# DC.net
KiCad netlist of a schematic drawn in Altium Designer
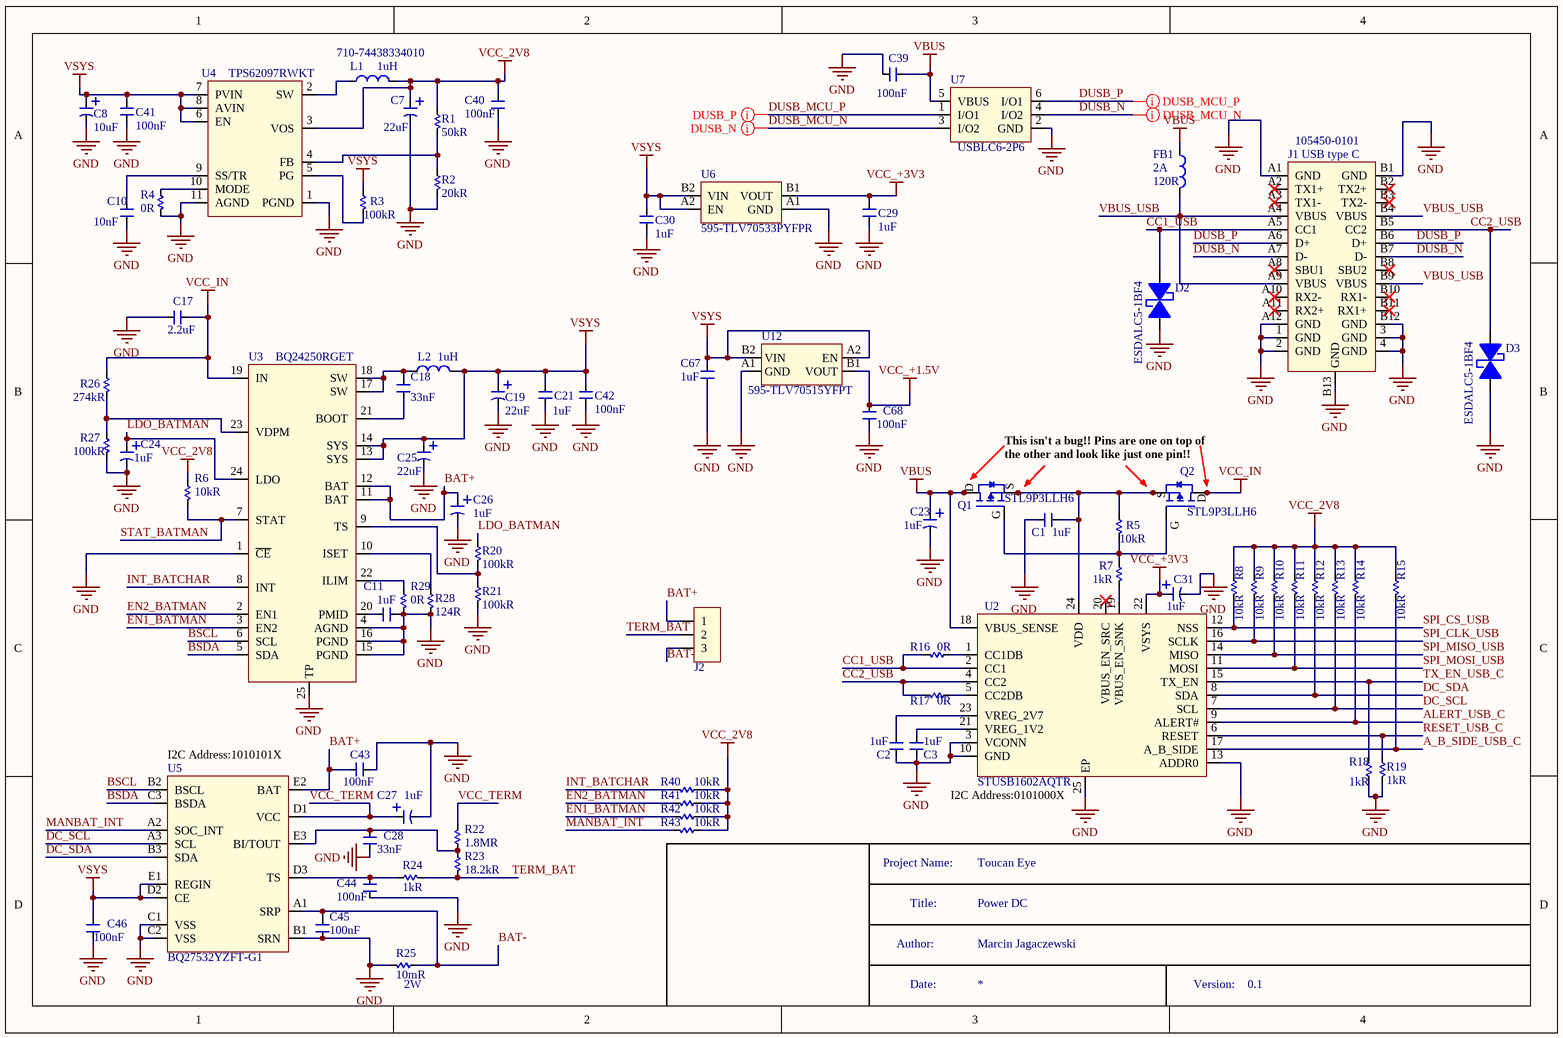
[diagram p0: DC.SchDoc]

(export (version "E")
  (design (tool "Eeschema 10.0.6"))
  (components
    (comp (ref "C1")
      (value "C0402_1uF_TMK105BJ105MV-F")
      (footprint "C_0402")
      (description "CAP CER 1UF 25V X5R 0402")
      (fields
        (field (name "MANUFACTURER") "Taiyo Yuden")
        (field (name "MANUFACTURER PART NUMBER") "TMK105BJ105MV-F")
        (field (name "CAPACITANCE") "1uF")
      )
      (libsource (lib "CAP") (part "C0402_1uF_TMK105BJ105MV-F"))
    )
    (comp (ref "C2")
      (value "C0402_1uF_TMK105BJ105MV-F")
      (footprint "C_0402")
      (description "CAP CER 1UF 25V X5R 0402")
      (fields
        (field (name "MANUFACTURER") "Taiyo Yuden")
        (field (name "MANUFACTURER PART NUMBER") "TMK105BJ105MV-F")
        (field (name "CAPACITANCE") "1uF")
      )
      (libsource (lib "CAP") (part "C0402_1uF_TMK105BJ105MV-F"))
    )
    (comp (ref "C3")
      (value "C0402_1uF_TMK105BJ105MV-F")
      (footprint "C_0402")
      (description "CAP CER 1UF 25V X5R 0402")
      (fields
        (field (name "MANUFACTURER") "Taiyo Yuden")
        (field (name "MANUFACTURER PART NUMBER") "TMK105BJ105MV-F")
        (field (name "CAPACITANCE") "1uF")
      )
      (libsource (lib "CAP") (part "C0402_1uF_TMK105BJ105MV-F"))
    )
    (comp (ref "C7")
      (value "C_22u_TANTAL_A_T491A226K006AT")
      (footprint "C_3216")
      (description "Cap Tant Solid 22uF 6.3V A CASE 10% (3.2 X 1.6 X 1.6mm) SMD 3216-18 4 Ohm 125C T/R")
      (fields
        (field (name "MANUFACTURER") "KEMET")
        (field (name "MANUFACTURER PART NUMBER") "T491A226K006AT")
        (field (name "CAPACITANCE") "22uF")
      )
      (libsource (lib "CAP") (part "C_22u_TANTAL_A_T491A226K006AT"))
    )
    (comp (ref "C8")
      (value "C_10u_TANTAL_A_T491A106K010AT7280")
      (footprint "C_3216")
      (description "CAP TANT 10UF 10V 10% 1206")
      (fields
        (field (name "MANUFACTURER") "KEMET")
        (field (name "MANUFACTURER PART NUMBER") "T491A106K010AT7280")
        (field (name "CAPACITANCE") "10uF")
      )
      (libsource (lib "CAP") (part "C_10u_TANTAL_A_T491A106K010AT7280"))
    )
    (comp (ref "C10")
      (value "C0402_10n_C0402C103K4PACTU")
      (footprint "C_0402")
      (description ".010UF 16.0V")
      (fields
        (field (name "MANUFACTURER") "KEMET")
        (field (name "MANUFACTURER PART NUMBER") "C0402C103K4PACTU")
        (field (name "CAPACITANCE") "10nF")
      )
      (libsource (lib "CAP") (part "C0402_10n_C0402C103K4PACTU"))
    )
    (comp (ref "C11")
      (value "C0402_1uF_TMK105BJ105MV-F")
      (footprint "C_0402")
      (description "CAP CER 1UF 25V X5R 0402")
      (fields
        (field (name "MANUFACTURER") "Taiyo Yuden")
        (field (name "MANUFACTURER PART NUMBER") "TMK105BJ105MV-F")
        (field (name "CAPACITANCE") "1uF")
      )
      (libsource (lib "CAP") (part "C0402_1uF_TMK105BJ105MV-F"))
    )
    (comp (ref "C17")
      (value "C0402_2.2u_GRT155R61E225KE13D")
      (footprint "C_0402")
      (description "2.2µF 25V Ceramic Capacitor X5R 0402 (1005 Metric) 0.039\" L x 0.020\" W (1.00mm x 0.50mm)")
      (fields
        (field (name "MANUFACTURER") "Murata")
        (field (name "MANUFACTURER PART NUMBER") "GRT155R61E225KE13D")
        (field (name "CAPACITANCE") "2.2uF")
      )
      (libsource (lib "CAP") (part "C0402_2.2u_GRT155R61E225KE13D"))
    )
    (comp (ref "C18")
      (value "C0402_33n_GCM155R71E333KA55D")
      (footprint "C_0402")
      (description "Multilayer Ceramic Capacitors MLCC - SMD/SMT .033uF 25Volts 10%")
      (fields
        (field (name "MANUFACTURER") "Murata")
        (field (name "MANUFACTURER PART NUMBER") "GCM155R71E333KA55D")
        (field (name "CAPACITANCE") "33nF")
      )
      (libsource (lib "CAP") (part "C0402_33n_GCM155R71E333KA55D"))
    )
    (comp (ref "C19")
      (value "C_22u_TANTAL_A_T491A226K006AT")
      (footprint "C_3216")
      (description "Cap Tant Solid 22uF 6.3V A CASE 10% (3.2 X 1.6 X 1.6mm) SMD 3216-18 4 Ohm 125C T/R")
      (fields
        (field (name "MANUFACTURER") "KEMET")
        (field (name "MANUFACTURER PART NUMBER") "T491A226K006AT")
        (field (name "CAPACITANCE") "22uF")
      )
      (libsource (lib "CAP") (part "C_22u_TANTAL_A_T491A226K006AT"))
    )
    (comp (ref "C21")
      (value "C0402_1uF_TMK105BJ105MV-F")
      (footprint "C_0402")
      (description "CAP CER 1UF 25V X5R 0402")
      (fields
        (field (name "MANUFACTURER") "Taiyo Yuden")
        (field (name "MANUFACTURER PART NUMBER") "TMK105BJ105MV-F")
        (field (name "CAPACITANCE") "1uF")
      )
      (libsource (lib "CAP") (part "C0402_1uF_TMK105BJ105MV-F"))
    )
    (comp (ref "C23")
      (value "C_1u_TANTAL_A_293D105X0025A2TE3")
      (footprint "C_3216")
      (description "CAP TANT 1UF 25V 20% 1206")
      (fields
        (field (name "MANUFACTURER") "Vishay Sprague")
        (field (name "MANUFACTURER PART NUMBER") "293D105X0025A2TE3")
        (field (name "CAPACITANCE") "1uF")
      )
      (libsource (lib "CAP") (part "C_1u_TANTAL_A_293D105X0025A2TE3"))
    )
    (comp (ref "C24")
      (value "C_1u_TANTAL_A_293D105X0025A2TE3")
      (footprint "C_3216")
      (description "CAP TANT 1UF 25V 20% 1206")
      (fields
        (field (name "MANUFACTURER") "Vishay Sprague")
        (field (name "MANUFACTURER PART NUMBER") "293D105X0025A2TE3")
        (field (name "CAPACITANCE") "1uF")
      )
      (libsource (lib "CAP") (part "C_1u_TANTAL_A_293D105X0025A2TE3"))
    )
    (comp (ref "C25")
      (value "C_22u_TANTAL_A_T491A226K006AT")
      (footprint "C_3216")
      (description "Cap Tant Solid 22uF 6.3V A CASE 10% (3.2 X 1.6 X 1.6mm) SMD 3216-18 4 Ohm 125C T/R")
      (fields
        (field (name "MANUFACTURER") "KEMET")
        (field (name "MANUFACTURER PART NUMBER") "T491A226K006AT")
        (field (name "CAPACITANCE") "22uF")
      )
      (libsource (lib "CAP") (part "C_22u_TANTAL_A_T491A226K006AT"))
    )
    (comp (ref "C26")
      (value "C_1u_TANTAL_A_293D105X0025A2TE3")
      (footprint "C_3216")
      (description "CAP TANT 1UF 25V 20% 1206")
      (fields
        (field (name "MANUFACTURER") "Vishay Sprague")
        (field (name "MANUFACTURER PART NUMBER") "293D105X0025A2TE3")
        (field (name "CAPACITANCE") "1uF")
      )
      (libsource (lib "CAP") (part "C_1u_TANTAL_A_293D105X0025A2TE3"))
    )
    (comp (ref "C27")
      (value "C_1u_TANTAL_A_293D105X0025A2TE3")
      (footprint "C_3216")
      (description "CAP TANT 1UF 25V 20% 1206")
      (fields
        (field (name "MANUFACTURER") "Vishay Sprague")
        (field (name "MANUFACTURER PART NUMBER") "293D105X0025A2TE3")
        (field (name "CAPACITANCE") "1uF")
      )
      (libsource (lib "CAP") (part "C_1u_TANTAL_A_293D105X0025A2TE3"))
    )
    (comp (ref "C28")
      (value "C0402_33n_GCM155R71E333KA55D")
      (footprint "C_0402")
      (description "Multilayer Ceramic Capacitors MLCC - SMD/SMT .033uF 25Volts 10%")
      (fields
        (field (name "MANUFACTURER") "Murata")
        (field (name "MANUFACTURER PART NUMBER") "GCM155R71E333KA55D")
        (field (name "CAPACITANCE") "33nF")
      )
      (libsource (lib "CAP") (part "C0402_33n_GCM155R71E333KA55D"))
    )
    (comp (ref "C29")
      (value "C0402_1uF_TMK105BJ105MV-F")
      (footprint "C_0402")
      (description "CAP CER 1UF 25V X5R 0402")
      (fields
        (field (name "MANUFACTURER") "Taiyo Yuden")
        (field (name "MANUFACTURER PART NUMBER") "TMK105BJ105MV-F")
        (field (name "CAPACITANCE") "1uF")
      )
      (libsource (lib "CAP") (part "C0402_1uF_TMK105BJ105MV-F"))
    )
    (comp (ref "C30")
      (value "C0402_1uF_TMK105BJ105MV-F")
      (footprint "C_0402")
      (description "CAP CER 1UF 25V X5R 0402")
      (fields
        (field (name "MANUFACTURER") "Taiyo Yuden")
        (field (name "MANUFACTURER PART NUMBER") "TMK105BJ105MV-F")
        (field (name "CAPACITANCE") "1uF")
      )
      (libsource (lib "CAP") (part "C0402_1uF_TMK105BJ105MV-F"))
    )
    (comp (ref "C31")
      (value "C_1u_TANTAL_A_293D105X0025A2TE3")
      (footprint "C_3216")
      (description "CAP TANT 1UF 25V 20% 1206")
      (fields
        (field (name "MANUFACTURER") "Vishay Sprague")
        (field (name "MANUFACTURER PART NUMBER") "293D105X0025A2TE3")
        (field (name "CAPACITANCE") "1uF")
      )
      (libsource (lib "CAP") (part "C_1u_TANTAL_A_293D105X0025A2TE3"))
    )
    (comp (ref "C39")
      (value "C0201_100n_GRM033R6YA104KE14D")
      (footprint "C_0201")
      (description "Multilayer Ceramic Capacitors MLCC - SMD/SMT 0201 0.10uF 35volts *Derate Voltage/Temp")
      (fields
        (field (name "MANUFACTURER") "Murata")
        (field (name "MANUFACTURER PART NUMBER") "GRM033R6YA104KE14D")
        (field (name "CAPACITANCE") "100nF")
      )
      (libsource (lib "CAP") (part "C0201_100n_GRM033R6YA104KE14D"))
    )
    (comp (ref "C40")
      (value "C0201_100n_GRM033R6YA104KE14D")
      (footprint "C_0201")
      (description "Multilayer Ceramic Capacitors MLCC - SMD/SMT 0201 0.10uF 35volts *Derate Voltage/Temp")
      (fields
        (field (name "MANUFACTURER") "Murata")
        (field (name "MANUFACTURER PART NUMBER") "GRM033R6YA104KE14D")
        (field (name "CAPACITANCE") "100nF")
      )
      (libsource (lib "CAP") (part "C0201_100n_GRM033R6YA104KE14D"))
    )
    (comp (ref "C41")
      (value "C0201_100n_GRM033R6YA104KE14D")
      (footprint "C_0201")
      (description "Multilayer Ceramic Capacitors MLCC - SMD/SMT 0201 0.10uF 35volts *Derate Voltage/Temp")
      (fields
        (field (name "MANUFACTURER") "Murata")
        (field (name "MANUFACTURER PART NUMBER") "GRM033R6YA104KE14D")
        (field (name "CAPACITANCE") "100nF")
      )
      (libsource (lib "CAP") (part "C0201_100n_GRM033R6YA104KE14D"))
    )
    (comp (ref "C42")
      (value "C0201_100n_GRM033R6YA104KE14D")
      (footprint "C_0201")
      (description "Multilayer Ceramic Capacitors MLCC - SMD/SMT 0201 0.10uF 35volts *Derate Voltage/Temp")
      (fields
        (field (name "MANUFACTURER") "Murata")
        (field (name "MANUFACTURER PART NUMBER") "GRM033R6YA104KE14D")
        (field (name "CAPACITANCE") "100nF")
      )
      (libsource (lib "CAP") (part "C0201_100n_GRM033R6YA104KE14D"))
    )
    (comp (ref "C43")
      (value "C0201_100n_GRM033R6YA104KE14D")
      (footprint "C_0201")
      (description "Multilayer Ceramic Capacitors MLCC - SMD/SMT 0201 0.10uF 35volts *Derate Voltage/Temp")
      (fields
        (field (name "MANUFACTURER") "Murata")
        (field (name "MANUFACTURER PART NUMBER") "GRM033R6YA104KE14D")
        (field (name "CAPACITANCE") "100nF")
      )
      (libsource (lib "CAP") (part "C0201_100n_GRM033R6YA104KE14D"))
    )
    (comp (ref "C44")
      (value "C0201_100n_GRM033R6YA104KE14D")
      (footprint "C_0201")
      (description "Multilayer Ceramic Capacitors MLCC - SMD/SMT 0201 0.10uF 35volts *Derate Voltage/Temp")
      (fields
        (field (name "MANUFACTURER") "Murata")
        (field (name "MANUFACTURER PART NUMBER") "GRM033R6YA104KE14D")
        (field (name "CAPACITANCE") "100nF")
      )
      (libsource (lib "CAP") (part "C0201_100n_GRM033R6YA104KE14D"))
    )
    (comp (ref "C45")
      (value "C0201_100n_GRM033R6YA104KE14D")
      (footprint "C_0201")
      (description "Multilayer Ceramic Capacitors MLCC - SMD/SMT 0201 0.10uF 35volts *Derate Voltage/Temp")
      (fields
        (field (name "MANUFACTURER") "Murata")
        (field (name "MANUFACTURER PART NUMBER") "GRM033R6YA104KE14D")
        (field (name "CAPACITANCE") "100nF")
      )
      (libsource (lib "CAP") (part "C0201_100n_GRM033R6YA104KE14D"))
    )
    (comp (ref "C46")
      (value "C0201_100n_GRM033R6YA104KE14D")
      (footprint "C_0201")
      (description "Multilayer Ceramic Capacitors MLCC - SMD/SMT 0201 0.10uF 35volts *Derate Voltage/Temp")
      (fields
        (field (name "MANUFACTURER") "Murata")
        (field (name "MANUFACTURER PART NUMBER") "GRM033R6YA104KE14D")
        (field (name "CAPACITANCE") "100nF")
      )
      (libsource (lib "CAP") (part "C0201_100n_GRM033R6YA104KE14D"))
    )
    (comp (ref "C67")
      (value "C0402_1uF_TMK105BJ105MV-F")
      (footprint "C_0402")
      (description "CAP CER 1UF 25V X5R 0402")
      (fields
        (field (name "MANUFACTURER") "Taiyo Yuden")
        (field (name "MANUFACTURER PART NUMBER") "TMK105BJ105MV-F")
        (field (name "CAPACITANCE") "1uF")
      )
      (libsource (lib "CAP") (part "C0402_1uF_TMK105BJ105MV-F"))
    )
    (comp (ref "C68")
      (value "C0201_100n_GRM033R6YA104KE14D")
      (footprint "C_0201")
      (description "Multilayer Ceramic Capacitors MLCC - SMD/SMT 0201 0.10uF 35volts *Derate Voltage/Temp")
      (fields
        (field (name "MANUFACTURER") "Murata")
        (field (name "MANUFACTURER PART NUMBER") "GRM033R6YA104KE14D")
        (field (name "CAPACITANCE") "100nF")
      )
      (libsource (lib "CAP") (part "C0201_100n_GRM033R6YA104KE14D"))
    )
    (comp (ref "D2")
      (value "ESDALC5-1BF4")
      (footprint "DFN35P60X32-2N")
      (description "ESD Suppressor TVS 30KV 2-Pin Case 0201 T/R")
      (fields (field (name "MANUFACTURER") "STMicroelectronics"))
      (libsource (lib "DIO") (part "ESDALC5-1BF4"))
    )
    (comp (ref "D3")
      (value "ESDALC5-1BF4")
      (footprint "DFN35P60X32-2N")
      (description "ESD Suppressor TVS 30KV 2-Pin Case 0201 T/R")
      (fields (field (name "MANUFACTURER") "STMicroelectronics"))
      (libsource (lib "DIO") (part "ESDALC5-1BF4"))
    )
    (comp (ref "FB1")
      (value "BLM18PG-121SN1D")
      (footprint "L_0603")
      (description "Ferrite Beads Multi-Layer 120Ohm 25% 100MHz 2A 50mOhm DCR 0603 Paper T/R")
      (fields
        (field (name "MANUFACTURER") "Murata")
        (field (name "TOLERANCE") "25%")
        (field (name "DC CURRENT") "2A")
        (field (name "IMPEDANCE") "120R")
      )
      (libsource (lib "IND") (part "BLM18PG-121SN1D"))
    )
    (comp (ref "J1")
      (value "105450-0101")
      (footprint "USB TYPE C (MOLEX)")
      (fields (field (name "MANUFACTURER") "Molex") (field (name "CONNECTOR TYPE") "USB type C"))
      (libsource (lib "CONN") (part "105450-0101"))
    )
    (comp (ref "J2")
      (value "Goldpin 3x1.27mm NDI")
      (footprint "HEADER 3x1.27mm")
      (libsource (lib "Holes") (part "Goldpin 3x1.27mm NDI"))
    )
    (comp (ref "L1")
      (value "L_1u_3x3_74438334010")
      (footprint "L_3x3")
      (fields
        (field (name "MANUFACTURER") "Wurth Electronics")
        (field (name "MANUFACTURER PART NUMBER") "74438334010")
        (field (name "TOLERANCE") "20%")
        (field (name "INDUCTANCE") "1uH")
        (field (name "SUPPLIER PART NUMBER 1") "710-74438334010")
      )
      (libsource (lib "IND") (part "L_1u_3x3_74438334010"))
    )
    (comp (ref "L2")
      (value "l_1U_3X3_74438336010")
      (footprint "L_3x3")
      (fields
        (field (name "MANUFACTURER") "Wurth Electronics")
        (field (name "MANUFACTURER PART NUMBER") "74438336010")
        (field (name "TOLERANCE") "20%")
        (field (name "INDUCTANCE") "1uH")
      )
      (libsource (lib "IND") (part "l_1U_3X3_74438336010"))
    )
    (comp (ref "Q1")
      (value "STL9P3LLH6")
      (footprint "PowerFLAT")
      (description "POWER MOSFET")
      (fields (field (name "MANUFACTURER") "STMicroelectronics"))
      (libsource (lib "DIO") (part "STL9P3LLH6"))
    )
    (comp (ref "Q2")
      (value "STL9P3LLH6")
      (footprint "PowerFLAT")
      (description "POWER MOSFET")
      (fields (field (name "MANUFACTURER") "STMicroelectronics"))
      (libsource (lib "DIO") (part "STL9P3LLH6"))
    )
    (comp (ref "R1")
      (value "R0402_50k_CRCW040250K0FKED")
      (footprint "R_0402")
      (description "Thick Film Resistors - SMD 1/16watt 50Kohms 1% Non Standard")
      (fields
        (field (name "MANUFACTURER") "Vishay Dale")
        (field (name "MANUFACTURER PART NUMBER") "CRCW040250K0FKED")
        (field (name "RESISTANCE") "50kR")
      )
      (libsource (lib "RES") (part "R0402_50k_CRCW040250K0FKED"))
    )
    (comp (ref "R2")
      (value "R0402_20k_ERJ-2RKF2002X")
      (footprint "R_0402")
      (description "Res Thick Film 0402 20K Ohm 1% 0.1W(1/10W) ±100ppm/C Molded SMD Automotive T/R")
      (fields
        (field (name "MANUFACTURER") "Panasonic ECG")
        (field (name "MANUFACTURER PART NUMBER") "ERJ-2RKF2002X")
        (field (name "RESISTANCE") "20kR")
      )
      (libsource (lib "RES") (part "R0402_20k_ERJ-2RKF2002X"))
    )
    (comp (ref "R3")
      (value "R0402_100k_ERJ-2RKF1003X")
      (footprint "R_0402")
      (description "Res Thick Film 0402 100K Ohm 1% 0.1W(1/10W) ±100ppm/C Molded SMD Automotive Punched T/R")
      (fields
        (field (name "MANUFACTURER") "Panasonic ECG")
        (field (name "MANUFACTURER PART NUMBER") "ERJ-2RKF1003X")
        (field (name "RESISTANCE") "100kR")
      )
      (libsource (lib "RES") (part "R0402_100k_ERJ-2RKF1003X"))
    )
    (comp (ref "R4")
      (value "R0402_0ohm_RC0402FR-070RL")
      (footprint "R_0402")
      (description "Thick Film Resistors - SMD 0.0ohm 1%")
      (fields
        (field (name "MANUFACTURER") "Yageo")
        (field (name "MANUFACTURER PART NUMBER") "RC0402FR-070RL")
        (field (name "RESISTANCE") "0R")
      )
      (libsource (lib "RES") (part "R0402_0ohm_RC0402FR-070RL"))
    )
    (comp (ref "R5")
      (value "R0201_10k_ERJ-1GNF1002C")
      (footprint "R_0201")
      (description "RESISTOR, 0201, 0.05W, 1%, 10K")
      (fields
        (field (name "MANUFACTURER") "Panasonic ECG")
        (field (name "MANUFACTURER PART NUMBER") "ERJ-1GNF1002C")
        (field (name "RESISTANCE") "10kR")
      )
      (libsource (lib "RES") (part "R0201_10k_ERJ-1GNF1002C"))
    )
    (comp (ref "R6")
      (value "R0201_10k_ERJ-1GNF1002C")
      (footprint "R_0201")
      (description "RESISTOR, 0201, 0.05W, 1%, 10K")
      (fields
        (field (name "MANUFACTURER") "Panasonic ECG")
        (field (name "MANUFACTURER PART NUMBER") "ERJ-1GNF1002C")
        (field (name "RESISTANCE") "10kR")
      )
      (libsource (lib "RES") (part "R0201_10k_ERJ-1GNF1002C"))
    )
    (comp (ref "R7")
      (value "R0201_1k_ERJ-1GNF1001C")
      (footprint "R_0201")
      (description "RESISTOR, 0201, 0.05W, 1%, 1K")
      (fields
        (field (name "MANUFACTURER") "Panasonic ECG")
        (field (name "MANUFACTURER PART NUMBER") "ERJ-1GNF1001C")
        (field (name "RESISTANCE") "1kR")
      )
      (libsource (lib "RES") (part "R0201_1k_ERJ-1GNF1001C"))
    )
    (comp (ref "R8")
      (value "R0201_10k_ERJ-1GNF1002C")
      (footprint "R_0201")
      (description "RESISTOR, 0201, 0.05W, 1%, 10K")
      (fields
        (field (name "MANUFACTURER") "Panasonic ECG")
        (field (name "MANUFACTURER PART NUMBER") "ERJ-1GNF1002C")
        (field (name "RESISTANCE") "10kR")
      )
      (libsource (lib "RES") (part "R0201_10k_ERJ-1GNF1002C"))
    )
    (comp (ref "R9")
      (value "R0201_10k_ERJ-1GNF1002C")
      (footprint "R_0201")
      (description "RESISTOR, 0201, 0.05W, 1%, 10K")
      (fields
        (field (name "MANUFACTURER") "Panasonic ECG")
        (field (name "MANUFACTURER PART NUMBER") "ERJ-1GNF1002C")
        (field (name "RESISTANCE") "10kR")
      )
      (libsource (lib "RES") (part "R0201_10k_ERJ-1GNF1002C"))
    )
    (comp (ref "R10")
      (value "R0201_10k_ERJ-1GNF1002C")
      (footprint "R_0201")
      (description "RESISTOR, 0201, 0.05W, 1%, 10K")
      (fields
        (field (name "MANUFACTURER") "Panasonic ECG")
        (field (name "MANUFACTURER PART NUMBER") "ERJ-1GNF1002C")
        (field (name "RESISTANCE") "10kR")
      )
      (libsource (lib "RES") (part "R0201_10k_ERJ-1GNF1002C"))
    )
    (comp (ref "R11")
      (value "R0201_10k_ERJ-1GNF1002C")
      (footprint "R_0201")
      (description "RESISTOR, 0201, 0.05W, 1%, 10K")
      (fields
        (field (name "MANUFACTURER") "Panasonic ECG")
        (field (name "MANUFACTURER PART NUMBER") "ERJ-1GNF1002C")
        (field (name "RESISTANCE") "10kR")
      )
      (libsource (lib "RES") (part "R0201_10k_ERJ-1GNF1002C"))
    )
    (comp (ref "R12")
      (value "R0201_10k_ERJ-1GNF1002C")
      (footprint "R_0201")
      (description "RESISTOR, 0201, 0.05W, 1%, 10K")
      (fields
        (field (name "MANUFACTURER") "Panasonic ECG")
        (field (name "MANUFACTURER PART NUMBER") "ERJ-1GNF1002C")
        (field (name "RESISTANCE") "10kR")
      )
      (libsource (lib "RES") (part "R0201_10k_ERJ-1GNF1002C"))
    )
    (comp (ref "R13")
      (value "R0201_10k_ERJ-1GNF1002C")
      (footprint "R_0201")
      (description "RESISTOR, 0201, 0.05W, 1%, 10K")
      (fields
        (field (name "MANUFACTURER") "Panasonic ECG")
        (field (name "MANUFACTURER PART NUMBER") "ERJ-1GNF1002C")
        (field (name "RESISTANCE") "10kR")
      )
      (libsource (lib "RES") (part "R0201_10k_ERJ-1GNF1002C"))
    )
    (comp (ref "R14")
      (value "R0201_10k_ERJ-1GNF1002C")
      (footprint "R_0201")
      (description "RESISTOR, 0201, 0.05W, 1%, 10K")
      (fields
        (field (name "MANUFACTURER") "Panasonic ECG")
        (field (name "MANUFACTURER PART NUMBER") "ERJ-1GNF1002C")
        (field (name "RESISTANCE") "10kR")
      )
      (libsource (lib "RES") (part "R0201_10k_ERJ-1GNF1002C"))
    )
    (comp (ref "R15")
      (value "R0201_10k_ERJ-1GNF1002C")
      (footprint "R_0201")
      (description "RESISTOR, 0201, 0.05W, 1%, 10K")
      (fields
        (field (name "MANUFACTURER") "Panasonic ECG")
        (field (name "MANUFACTURER PART NUMBER") "ERJ-1GNF1002C")
        (field (name "RESISTANCE") "10kR")
      )
      (libsource (lib "RES") (part "R0201_10k_ERJ-1GNF1002C"))
    )
    (comp (ref "R16")
      (value "R0201_0_ERJ-1GN0R00C")
      (footprint "R_0201")
      (description "RES SMD 0.0OHM JUMPER 1/20W 0201")
      (fields
        (field (name "MANUFACTURER") "Panasonic")
        (field (name "MANUFACTURER PART NUMBER") "ERJ-1GN0R00C")
        (field (name "RESISTANCE") "0R")
      )
      (libsource (lib "RES") (part "R0201_0_ERJ-1GN0R00C"))
    )
    (comp (ref "R17")
      (value "R0201_0_ERJ-1GN0R00C")
      (footprint "R_0201")
      (description "RES SMD 0.0OHM JUMPER 1/20W 0201")
      (fields
        (field (name "MANUFACTURER") "Panasonic")
        (field (name "MANUFACTURER PART NUMBER") "ERJ-1GN0R00C")
        (field (name "RESISTANCE") "0R")
      )
      (libsource (lib "RES") (part "R0201_0_ERJ-1GN0R00C"))
    )
    (comp (ref "R18")
      (value "R0201_1k_ERJ-1GNF1001C")
      (footprint "R_0201")
      (description "RESISTOR, 0201, 0.05W, 1%, 1K")
      (fields
        (field (name "MANUFACTURER") "Panasonic ECG")
        (field (name "MANUFACTURER PART NUMBER") "ERJ-1GNF1001C")
        (field (name "RESISTANCE") "1kR")
      )
      (libsource (lib "RES") (part "R0201_1k_ERJ-1GNF1001C"))
    )
    (comp (ref "R19")
      (value "R0201_1k_ERJ-1GNF1001C")
      (footprint "R_0201")
      (description "RESISTOR, 0201, 0.05W, 1%, 1K")
      (fields
        (field (name "MANUFACTURER") "Panasonic ECG")
        (field (name "MANUFACTURER PART NUMBER") "ERJ-1GNF1001C")
        (field (name "RESISTANCE") "1kR")
      )
      (libsource (lib "RES") (part "R0201_1k_ERJ-1GNF1001C"))
    )
    (comp (ref "R20")
      (value "R0402_100k_ERJ-2RKF1003X")
      (footprint "R_0402")
      (description "Res Thick Film 0402 100K Ohm 1% 0.1W(1/10W) ±100ppm/C Molded SMD Automotive Punched T/R")
      (fields
        (field (name "MANUFACTURER") "Panasonic ECG")
        (field (name "MANUFACTURER PART NUMBER") "ERJ-2RKF1003X")
        (field (name "RESISTANCE") "100kR")
      )
      (libsource (lib "RES") (part "R0402_100k_ERJ-2RKF1003X"))
    )
    (comp (ref "R21")
      (value "R0402_100k_ERJ-2RKF1003X")
      (footprint "R_0402")
      (description "Res Thick Film 0402 100K Ohm 1% 0.1W(1/10W) ±100ppm/C Molded SMD Automotive Punched T/R")
      (fields
        (field (name "MANUFACTURER") "Panasonic ECG")
        (field (name "MANUFACTURER PART NUMBER") "ERJ-2RKF1003X")
        (field (name "RESISTANCE") "100kR")
      )
      (libsource (lib "RES") (part "R0402_100k_ERJ-2RKF1003X"))
    )
    (comp (ref "R22")
      (value "R0402_1.8Mohm_ERJ-2GEJ185X")
      (footprint "R_0402")
      (description "RESISTOR, THICK FILM, 0402, 1.8MOHM, 5%, 100mW")
      (fields
        (field (name "MANUFACTURER") "Panasonic ECG")
        (field (name "MANUFACTURER PART NUMBER") "ERJ-2GEJ185X")
        (field (name "RESISTANCE") "1.8MR")
      )
      (libsource (lib "RES") (part "R0402_1.8Mohm_ERJ-2GEJ185X"))
    )
    (comp (ref "R23")
      (value "R0402_18.2k_ERJ-2RKF1822X")
      (footprint "R_0402")
      (description "RESISTOR, THICK FILM, 18.2KOHM, 100mW, ± 1%")
      (fields
        (field (name "MANUFACTURER") "Panasonic ECG")
        (field (name "MANUFACTURER PART NUMBER") "ERJ-2RKF1822X")
        (field (name "RESISTANCE") "18.2kR")
      )
      (libsource (lib "RES") (part "R0402_18.2k_ERJ-2RKF1822X"))
    )
    (comp (ref "R24")
      (value "R0201_1k_ERJ-1GNF1001C")
      (footprint "R_0201")
      (description "RESISTOR, 0201, 0.05W, 1%, 1K")
      (fields
        (field (name "MANUFACTURER") "Panasonic ECG")
        (field (name "MANUFACTURER PART NUMBER") "ERJ-1GNF1001C")
        (field (name "RESISTANCE") "1kR")
      )
      (libsource (lib "RES") (part "R0201_1k_ERJ-1GNF1001C"))
    )
    (comp (ref "R25")
      (value "R2512_10m_WW25RR010FTL")
      (footprint "R2512")
      (fields
        (field (name "MANUFACTURER") "Walsin Technologies")
        (field (name "MANUFACTURER PART NUMBER") "WW25RR010FTL")
        (field (name "POWER RATING") "2W")
        (field (name "TOLERANCE") "1%")
        (field (name "RESISTANCE") "10mR")
      )
      (libsource (lib "RES") (part "R2512_10m_WW25RR010FTL"))
    )
    (comp (ref "R26")
      (value "R0402_274k_ERJ-2RKF2743X")
      (footprint "R_0402")
      (description "Res Thick Film 0402 274K Ohm 1% 0.1W(1/10W) ±100ppm/C Molded SMD Automotive Punched T/R")
      (fields
        (field (name "MANUFACTURER") "Panasonic ECG")
        (field (name "MANUFACTURER PART NUMBER") "ERJ-2RKF2743X")
        (field (name "RESISTANCE") "274kR")
      )
      (libsource (lib "RES") (part "R0402_274k_ERJ-2RKF2743X"))
    )
    (comp (ref "R27")
      (value "R0402_100k_ERJ-2RKF1003X")
      (footprint "R_0402")
      (description "Res Thick Film 0402 100K Ohm 1% 0.1W(1/10W) ±100ppm/C Molded SMD Automotive Punched T/R")
      (fields
        (field (name "MANUFACTURER") "Panasonic ECG")
        (field (name "MANUFACTURER PART NUMBER") "ERJ-2RKF1003X")
        (field (name "RESISTANCE") "100kR")
      )
      (libsource (lib "RES") (part "R0402_100k_ERJ-2RKF1003X"))
    )
    (comp (ref "R28")
      (value "R0402_124OHM_ERJ-2RKF1240X")
      (footprint "R_0402")
      (description "Res Thick Film 0402 124 Ohm 1% 0.1W(1/10W) ±100ppm/C Molded SMD Automotive Punched T/R")
      (fields
        (field (name "MANUFACTURER") "Panasonic ECG")
        (field (name "MANUFACTURER PART NUMBER") "ERJ-2RKF1240X")
        (field (name "RESISTANCE") "124R")
      )
      (libsource (lib "RES") (part "R0402_124OHM_ERJ-2RKF1240X"))
    )
    (comp (ref "R29")
      (value "R0402_0ohm_RC0402FR-070RL")
      (footprint "R_0402")
      (description "Thick Film Resistors - SMD 0.0ohm 1%")
      (fields
        (field (name "MANUFACTURER") "Yageo")
        (field (name "MANUFACTURER PART NUMBER") "RC0402FR-070RL")
        (field (name "RESISTANCE") "0R")
      )
      (libsource (lib "RES") (part "R0402_0ohm_RC0402FR-070RL"))
    )
    (comp (ref "R40")
      (value "R0201_10k_ERJ-1GNF1002C")
      (footprint "R_0201")
      (description "RESISTOR, 0201, 0.05W, 1%, 10K")
      (fields
        (field (name "MANUFACTURER") "Panasonic ECG")
        (field (name "MANUFACTURER PART NUMBER") "ERJ-1GNF1002C")
        (field (name "RESISTANCE") "10kR")
      )
      (libsource (lib "RES") (part "R0201_10k_ERJ-1GNF1002C"))
    )
    (comp (ref "R41")
      (value "R0201_10k_ERJ-1GNF1002C")
      (footprint "R_0201")
      (description "RESISTOR, 0201, 0.05W, 1%, 10K")
      (fields
        (field (name "MANUFACTURER") "Panasonic ECG")
        (field (name "MANUFACTURER PART NUMBER") "ERJ-1GNF1002C")
        (field (name "RESISTANCE") "10kR")
      )
      (libsource (lib "RES") (part "R0201_10k_ERJ-1GNF1002C"))
    )
    (comp (ref "R42")
      (value "R0201_10k_ERJ-1GNF1002C")
      (footprint "R_0201")
      (description "RESISTOR, 0201, 0.05W, 1%, 10K")
      (fields
        (field (name "MANUFACTURER") "Panasonic ECG")
        (field (name "MANUFACTURER PART NUMBER") "ERJ-1GNF1002C")
        (field (name "RESISTANCE") "10kR")
      )
      (libsource (lib "RES") (part "R0201_10k_ERJ-1GNF1002C"))
    )
    (comp (ref "R43")
      (value "R0201_10k_ERJ-1GNF1002C")
      (footprint "R_0201")
      (description "RESISTOR, 0201, 0.05W, 1%, 10K")
      (fields
        (field (name "MANUFACTURER") "Panasonic ECG")
        (field (name "MANUFACTURER PART NUMBER") "ERJ-1GNF1002C")
        (field (name "RESISTANCE") "10kR")
      )
      (libsource (lib "RES") (part "R0201_10k_ERJ-1GNF1002C"))
    )
    (comp (ref "U2")
      (value "STUSB1602AQTR")
      (footprint "QFN24")
      (fields (field (name "MANUFACTURER") "STMicroelectronics"))
      (libsource (lib "CHIP") (part "STUSB1602AQTR"))
    )
    (comp (ref "U3")
      (value "BQ24250RGET")
      (footprint "VQFN")
      (description "IC BATT CHARGER LI-ION 24VQFN")
      (fields (field (name "MANUFACTURER") "Texas Instruments"))
      (libsource (lib "CHIP") (part "BQ24250RGET"))
    )
    (comp (ref "U4")
      (value "TPS62097RWKT")
      (footprint "VQFN_11")
      (fields (field (name "MANUFACTURER") "Texas Instruments"))
      (libsource (lib "CHIP") (part "TPS62097RWKT"))
    )
    (comp (ref "U5")
      (value "BQ27532YZFT-G1")
      (footprint "DSBGA-15_PINS")
      (description "TEXAS INSTRUMENTS         BQ27532YZFT-G1             BATT GAS GAUGE & CTRL, LI-ION, DSBGA-15")
      (fields (field (name "MANUFACTURER") "Texas Instruments"))
      (libsource (lib "CHIP") (part "BQ27532YZFT-G1"))
    )
    (comp (ref "U6")
      (value "TLV70533PYFPR")
      (footprint "DSBGA")
      (fields
        (field (name "MANUFACTURER") "Texas Instruments")
        (field (name "SUPPLIER PART NUMBER 1") "595-TLV70533PYFPR")
      )
      (libsource (lib "CHIP") (part "TLV70533PYFPR"))
    )
    (comp (ref "U7")
      (value "USBLC6-2P6")
      (footprint "SOT-666")
      (description "TVS DIODE 5.25VWM 17VC SOT666")
      (fields
        (field (name "MANUFACTURER") "STMicroelectronics")
        (field (name "MANUFACTURER PART NUMBER") "USBLC6-2P6")
      )
      (libsource (lib "CHIP") (part "USBLC6-2P6"))
    )
    (comp (ref "U12")
      (value "TLV70515YFPT")
      (footprint "DSBGA")
      (description "LDO Voltage Regulators 200mA Lo IQ Lo-Noise LDO Reg")
      (fields
        (field (name "MANUFACTURER") "Texas Instruments")
        (field (name "SUPPLIER PART NUMBER 1") "595-TLV70515YFPT")
      )
      (libsource (lib "CHIP") (part "TLV70515YFPT"))
    )
  )
  (nets
    (net (code "1") (name "/ALERT_USB_C") (class "Default")
      (node (ref "R14") (pin "1") (pinfunction "1_1") (pintype "power_in"))
      (node (ref "U2") (pin "9") (pinfunction "ALERT#_9") (pintype "power_in"))
    )
    (net (code "2") (name "/A_B_SIDE_USB_C") (class "Default")
      (node (ref "R15") (pin "1") (pinfunction "1_1") (pintype "power_in"))
      (node (ref "U2") (pin "17") (pinfunction "A_B_SIDE_17") (pintype "power_in"))
    )
    (net (code "3") (name "/BAT+") (class "Default")
      (node (ref "C26") (pin "1") (pinfunction "1_1") (pintype "passive"))
      (node (ref "C43") (pin "2") (pinfunction "2_2") (pintype "passive"))
      (node (ref "J2") (pin "1") (pinfunction "1_1") (pintype "power_in"))
      (node (ref "U3") (pin "11") (pinfunction "BAT_11") (pintype "power_in"))
      (node (ref "U3") (pin "12") (pinfunction "BAT_12") (pintype "power_in"))
      (node (ref "U5") (pin "E2") (pinfunction "BAT_E2") (pintype "passive"))
    )
    (net (code "4") (name "/BAT-") (class "Default")
      (node (ref "C45") (pin "1") (pinfunction "1_1") (pintype "passive"))
      (node (ref "J2") (pin "3") (pinfunction "3_3") (pintype "power_in"))
      (node (ref "R25") (pin "2") (pinfunction "2_2") (pintype "power_in"))
      (node (ref "U5") (pin "A1") (pinfunction "SRP_A1") (pintype "passive"))
    )
    (net (code "5") (name "/BSCL") (class "Default")
      (node (ref "U3") (pin "6") (pinfunction "SCL_6") (pintype "power_in"))
      (node (ref "U5") (pin "B2") (pinfunction "BSCL_B2") (pintype "passive"))
    )
    (net (code "6") (name "/BSDA") (class "Default")
      (node (ref "U3") (pin "5") (pinfunction "SDA_5") (pintype "power_in"))
      (node (ref "U5") (pin "C3") (pinfunction "BSDA_C3") (pintype "passive"))
    )
    (net (code "7") (name "/CC1_USB") (class "Default")
      (node (ref "D2") (pin "2") (pinfunction "2_2") (pintype "power_in"))
      (node (ref "J1") (pin "A5") (pinfunction "CC1_A5") (pintype "passive"))
      (node (ref "R16") (pin "1") (pinfunction "1_1") (pintype "power_in"))
      (node (ref "U2") (pin "2") (pinfunction "CC1_2") (pintype "power_in"))
    )
    (net (code "8") (name "/CC2_USB") (class "Default")
      (node (ref "D3") (pin "2") (pinfunction "2_2") (pintype "power_in"))
      (node (ref "J1") (pin "B5") (pinfunction "CC2_B5") (pintype "passive"))
      (node (ref "R17") (pin "1") (pinfunction "1_1") (pintype "power_in"))
      (node (ref "U2") (pin "4") (pinfunction "CC2_4") (pintype "power_in"))
    )
    (net (code "9") (name "/DC_SCL") (class "Default")
      (node (ref "R13") (pin "1") (pinfunction "1_1") (pintype "power_in"))
      (node (ref "U2") (pin "7") (pinfunction "SCL_7") (pintype "power_in"))
      (node (ref "U5") (pin "A3") (pinfunction "SCL_A3") (pintype "passive"))
    )
    (net (code "10") (name "/DC_SDA") (class "Default")
      (node (ref "R12") (pin "1") (pinfunction "1_1") (pintype "power_in"))
      (node (ref "U2") (pin "8") (pinfunction "SDA_8") (pintype "power_in"))
      (node (ref "U5") (pin "B3") (pinfunction "SDA_B3") (pintype "passive"))
    )
    (net (code "11") (name "/DUSB_MCU_N") (class "Default")
      (node (ref "U7") (pin "3") (pinfunction "I/O2_3") (pintype "passive"))
    )
    (net (code "12") (name "/DUSB_MCU_P") (class "Default")
      (node (ref "U7") (pin "1") (pinfunction "I/O1_1") (pintype "passive"))
    )
    (net (code "13") (name "/DUSB_N") (class "Default")
      (node (ref "J1") (pin "A7") (pinfunction "D-_A7") (pintype "passive"))
      (node (ref "J1") (pin "B7") (pinfunction "D-_B7") (pintype "passive"))
      (node (ref "U7") (pin "4") (pinfunction "I/O2_4") (pintype "passive"))
    )
    (net (code "14") (name "/DUSB_P") (class "Default")
      (node (ref "J1") (pin "A6") (pinfunction "D+_A6") (pintype "passive"))
      (node (ref "J1") (pin "B6") (pinfunction "D+_B6") (pintype "passive"))
      (node (ref "U7") (pin "6") (pinfunction "I/O1_6") (pintype "passive"))
    )
    (net (code "15") (name "/EN1_BATMAN") (class "Default")
      (node (ref "R42") (pin "1") (pinfunction "1_1") (pintype "power_in"))
      (node (ref "U3") (pin "3") (pinfunction "EN2_3") (pintype "power_in"))
    )
    (net (code "16") (name "/EN2_BATMAN") (class "Default")
      (node (ref "R41") (pin "1") (pinfunction "1_1") (pintype "power_in"))
      (node (ref "U3") (pin "2") (pinfunction "EN1_2") (pintype "power_in"))
    )
    (net (code "17") (name "/INT_BATCHAR") (class "Default")
      (node (ref "R40") (pin "1") (pinfunction "1_1") (pintype "power_in"))
      (node (ref "U3") (pin "8") (pinfunction "INT_8") (pintype "power_in"))
    )
    (net (code "18") (name "/LDO_BATMAN") (class "Default")
      (node (ref "C24") (pin "1") (pinfunction "1_1") (pintype "passive"))
      (node (ref "R20") (pin "2") (pinfunction "2_2") (pintype "power_in"))
      (node (ref "U3") (pin "24") (pinfunction "LDO_24") (pintype "power_in"))
    )
    (net (code "19") (name "/MANBAT_INT") (class "Default")
      (node (ref "R43") (pin "1") (pinfunction "1_1") (pintype "power_in"))
      (node (ref "U5") (pin "A2") (pinfunction "SOC_INT_A2") (pintype "passive"))
    )
    (net (code "20") (name "/RESET_USB_C") (class "Default")
      (node (ref "R19") (pin "2") (pinfunction "2_2") (pintype "power_in"))
      (node (ref "U2") (pin "6") (pinfunction "RESET_6") (pintype "power_in"))
    )
    (net (code "21") (name "/SPI_CLK_USB") (class "Default")
      (node (ref "R9") (pin "1") (pinfunction "1_1") (pintype "power_in"))
      (node (ref "U2") (pin "16") (pinfunction "SCLK_16") (pintype "power_in"))
    )
    (net (code "22") (name "/SPI_CS_USB") (class "Default")
      (node (ref "R8") (pin "1") (pinfunction "1_1") (pintype "power_in"))
      (node (ref "U2") (pin "12") (pinfunction "NSS_12") (pintype "power_in"))
    )
    (net (code "23") (name "/SPI_MISO_USB") (class "Default")
      (node (ref "R10") (pin "1") (pinfunction "1_1") (pintype "power_in"))
      (node (ref "U2") (pin "14") (pinfunction "MISO_14") (pintype "power_in"))
    )
    (net (code "24") (name "/SPI_MOSI_USB") (class "Default")
      (node (ref "R11") (pin "1") (pinfunction "1_1") (pintype "power_in"))
      (node (ref "U2") (pin "11") (pinfunction "MOSI_11") (pintype "power_in"))
    )
    (net (code "25") (name "/STAT_BATMAN") (class "Default")
      (node (ref "R6") (pin "1") (pinfunction "1_1") (pintype "power_in"))
      (node (ref "U3") (pin "7") (pinfunction "STAT_7") (pintype "power_in"))
    )
    (net (code "26") (name "/TERM_BAT") (class "Default")
      (node (ref "J2") (pin "2") (pinfunction "2_2") (pintype "power_in"))
      (node (ref "R23") (pin "1") (pinfunction "1_1") (pintype "power_in"))
      (node (ref "R24") (pin "1") (pinfunction "1_1") (pintype "power_in"))
    )
    (net (code "27") (name "/TX_EN_USB_C") (class "Default")
      (node (ref "R18") (pin "1") (pinfunction "1_1") (pintype "power_in"))
      (node (ref "U2") (pin "15") (pinfunction "TX_EN_15") (pintype "power_in"))
    )
    (net (code "28") (name "/VBUS_USB") (class "Default")
      (node (ref "FB1") (pin "2") (pinfunction "Vcc_2") (pintype "passive"))
      (node (ref "J1") (pin "A4") (pinfunction "VBUS_A4") (pintype "passive"))
      (node (ref "J1") (pin "A9") (pinfunction "VBUS_A9") (pintype "passive"))
      (node (ref "J1") (pin "B4") (pinfunction "VBUS_B4") (pintype "passive"))
      (node (ref "J1") (pin "B9") (pinfunction "VBUS_B9") (pintype "passive"))
    )
    (net (code "29") (name "/VCC_TERM") (class "Default")
      (node (ref "C27") (pin "1") (pinfunction "1_1") (pintype "passive"))
      (node (ref "R22") (pin "1") (pinfunction "1_1") (pintype "power_in"))
      (node (ref "U5") (pin "D1") (pinfunction "VCC_D1") (pintype "passive"))
    )
    (net (code "30") (name "GND") (class "Default")
      (node (ref "C1") (pin "1") (pinfunction "1_1") (pintype "passive"))
      (node (ref "C10") (pin "1") (pinfunction "1_1") (pintype "passive"))
      (node (ref "C11") (pin "2") (pinfunction "2_2") (pintype "passive"))
      (node (ref "C17") (pin "2") (pinfunction "2_2") (pintype "passive"))
      (node (ref "C19") (pin "2") (pinfunction "2_2") (pintype "passive"))
      (node (ref "C2") (pin "1") (pinfunction "1_1") (pintype "passive"))
      (node (ref "C21") (pin "1") (pinfunction "1_1") (pintype "passive"))
      (node (ref "C23") (pin "2") (pinfunction "2_2") (pintype "passive"))
      (node (ref "C24") (pin "2") (pinfunction "2_2") (pintype "passive"))
      (node (ref "C25") (pin "2") (pinfunction "2_2") (pintype "passive"))
      (node (ref "C26") (pin "2") (pinfunction "2_2") (pintype "passive"))
      (node (ref "C27") (pin "2") (pinfunction "2_2") (pintype "passive"))
      (node (ref "C28") (pin "1") (pinfunction "1_1") (pintype "passive"))
      (node (ref "C29") (pin "1") (pinfunction "1_1") (pintype "passive"))
      (node (ref "C3") (pin "1") (pinfunction "1_1") (pintype "passive"))
      (node (ref "C30") (pin "2") (pinfunction "2_2") (pintype "passive"))
      (node (ref "C31") (pin "2") (pinfunction "2_2") (pintype "passive"))
      (node (ref "C39") (pin "1") (pinfunction "1_1") (pintype "passive"))
      (node (ref "C40") (pin "1") (pinfunction "1_1") (pintype "passive"))
      (node (ref "C41") (pin "2") (pinfunction "2_2") (pintype "passive"))
      (node (ref "C42") (pin "1") (pinfunction "1_1") (pintype "passive"))
      (node (ref "C43") (pin "1") (pinfunction "1_1") (pintype "passive"))
      (node (ref "C44") (pin "1") (pinfunction "1_1") (pintype "passive"))
      (node (ref "C45") (pin "2") (pinfunction "2_2") (pintype "passive"))
      (node (ref "C46") (pin "1") (pinfunction "1_1") (pintype "passive"))
      (node (ref "C67") (pin "1") (pinfunction "1_1") (pintype "passive"))
      (node (ref "C68") (pin "1") (pinfunction "1_1") (pintype "passive"))
      (node (ref "C7") (pin "2") (pinfunction "2_2") (pintype "passive"))
      (node (ref "C8") (pin "2") (pinfunction "2_2") (pintype "passive"))
      (node (ref "D2") (pin "1") (pinfunction "1_1") (pintype "power_in"))
      (node (ref "D3") (pin "1") (pinfunction "1_1") (pintype "power_in"))
      (node (ref "J1") (pin "1") (pinfunction "GND_1") (pintype "passive"))
      (node (ref "J1") (pin "2") (pinfunction "GND_2") (pintype "passive"))
      (node (ref "J1") (pin "3") (pinfunction "GND_3") (pintype "passive"))
      (node (ref "J1") (pin "4") (pinfunction "GND_4") (pintype "passive"))
      (node (ref "J1") (pin "A1") (pinfunction "GND_A1") (pintype "passive"))
      (node (ref "J1") (pin "A12") (pinfunction "GND_A12") (pintype "passive"))
      (node (ref "J1") (pin "B1") (pinfunction "GND_B1") (pintype "passive"))
      (node (ref "J1") (pin "B12") (pinfunction "GND_B12") (pintype "passive"))
      (node (ref "J1") (pin "B13") (pinfunction "GND_B13") (pintype "passive"))
      (node (ref "R18") (pin "2") (pinfunction "2_2") (pintype "power_in"))
      (node (ref "R19") (pin "1") (pinfunction "1_1") (pintype "power_in"))
      (node (ref "R2") (pin "1") (pinfunction "1_1") (pintype "power_in"))
      (node (ref "R21") (pin "1") (pinfunction "1_1") (pintype "power_in"))
      (node (ref "R25") (pin "1") (pinfunction "1_1") (pintype "power_in"))
      (node (ref "R27") (pin "1") (pinfunction "1_1") (pintype "power_in"))
      (node (ref "R28") (pin "1") (pinfunction "1_1") (pintype "power_in"))
      (node (ref "R29") (pin "1") (pinfunction "1_1") (pintype "power_in"))
      (node (ref "R4") (pin "1") (pinfunction "1_1") (pintype "power_in"))
      (node (ref "U12") (pin "A1") (pinfunction "GND_A1") (pintype "power_in"))
      (node (ref "U2") (pin "10") (pinfunction "GND_10") (pintype "power_in"))
      (node (ref "U2") (pin "13") (pinfunction "ADDR0_13") (pintype "power_in"))
      (node (ref "U2") (pin "25") (pinfunction "EP_25") (pintype "power_in"))
      (node (ref "U2") (pin "3") (pinfunction "VCONN_3") (pintype "power_in"))
      (node (ref "U3") (pin "1") (pinfunction "~{CE}_1") (pintype "power_in"))
      (node (ref "U3") (pin "15") (pinfunction "PGND_15") (pintype "power_in"))
      (node (ref "U3") (pin "16") (pinfunction "PGND_16") (pintype "power_in"))
      (node (ref "U3") (pin "25") (pinfunction "TP_25") (pintype "power_in"))
      (node (ref "U3") (pin "4") (pinfunction "AGND_4") (pintype "power_in"))
      (node (ref "U4") (pin "1") (pinfunction "PGND_1") (pintype "passive"))
      (node (ref "U4") (pin "11") (pinfunction "AGND_11") (pintype "passive"))
      (node (ref "U5") (pin "B1") (pinfunction "SRN_B1") (pintype "passive"))
      (node (ref "U5") (pin "C1") (pinfunction "VSS_C1") (pintype "passive"))
      (node (ref "U5") (pin "C2") (pinfunction "VSS_C2") (pintype "passive"))
      (node (ref "U6") (pin "A1") (pinfunction "GND_A1") (pintype "power_in"))
      (node (ref "U7") (pin "2") (pinfunction "GND_2") (pintype "passive"))
    )
    (net (code "31") (name "Net-(C18-Pad2)") (class "Default")
      (node (ref "C18") (pin "2") (pinfunction "2_2") (pintype "passive"))
      (node (ref "L2") (pin "1") (pinfunction "Vcc_1") (pintype "passive"))
      (node (ref "U3") (pin "17") (pinfunction "SW_17") (pintype "power_in"))
      (node (ref "U3") (pin "18") (pinfunction "SW_18") (pintype "power_in"))
    )
    (net (code "32") (name "Net-(Q1-G)") (class "Default")
      (node (ref "Q1") (pin "4") (pinfunction "G_4") (pintype "passive"))
      (node (ref "Q2") (pin "4") (pinfunction "G_4") (pintype "passive"))
      (node (ref "R5") (pin "1") (pinfunction "1_1") (pintype "power_in"))
      (node (ref "R7") (pin "2") (pinfunction "2_2") (pintype "power_in"))
    )
    (net (code "33") (name "Net-(U2-CC1DB)") (class "Default")
      (node (ref "R16") (pin "2") (pinfunction "2_2") (pintype "power_in"))
      (node (ref "U2") (pin "1") (pinfunction "CC1DB_1") (pintype "power_in"))
    )
    (net (code "34") (name "Net-(U2-CC2DB)") (class "Default")
      (node (ref "R17") (pin "2") (pinfunction "2_2") (pintype "power_in"))
      (node (ref "U2") (pin "5") (pinfunction "CC2DB_5") (pintype "power_in"))
    )
    (net (code "35") (name "Net-(U2-VBUS_EN_SNK)") (class "Default")
      (node (ref "R7") (pin "1") (pinfunction "1_1") (pintype "power_in"))
      (node (ref "U2") (pin "19") (pinfunction "VBUS_EN_SNK_19") (pintype "power_in"))
    )
    (net (code "36") (name "Net-(U2-VDD)") (class "Default")
      (node (ref "C1") (pin "2") (pinfunction "2_2") (pintype "passive"))
      (node (ref "Q1") (pin "1") (pinfunction "S_1") (pintype "passive"))
      (node (ref "Q1") (pin "2") (pinfunction "S_2") (pintype "passive"))
      (node (ref "Q1") (pin "3") (pinfunction "S_3") (pintype "passive"))
      (node (ref "Q2") (pin "1") (pinfunction "S_1") (pintype "passive"))
      (node (ref "Q2") (pin "2") (pinfunction "S_2") (pintype "passive"))
      (node (ref "Q2") (pin "3") (pinfunction "S_3") (pintype "passive"))
      (node (ref "R5") (pin "2") (pinfunction "2_2") (pintype "power_in"))
      (node (ref "U2") (pin "24") (pinfunction "VDD_24") (pintype "power_in"))
    )
    (net (code "37") (name "Net-(U2-VREG_1V2)") (class "Default")
      (node (ref "C3") (pin "2") (pinfunction "2_2") (pintype "passive"))
      (node (ref "U2") (pin "21") (pinfunction "VREG_1V2_21") (pintype "power_in"))
    )
    (net (code "38") (name "Net-(U2-VREG_2V7)") (class "Default")
      (node (ref "C2") (pin "2") (pinfunction "2_2") (pintype "passive"))
      (node (ref "U2") (pin "23") (pinfunction "VREG_2V7_23") (pintype "power_in"))
    )
    (net (code "39") (name "Net-(U3-BOOT)") (class "Default")
      (node (ref "C18") (pin "1") (pinfunction "1_1") (pintype "passive"))
      (node (ref "U3") (pin "21") (pinfunction "BOOT_21") (pintype "power_in"))
    )
    (net (code "40") (name "Net-(U3-ILIM)") (class "Default")
      (node (ref "R29") (pin "2") (pinfunction "2_2") (pintype "power_in"))
      (node (ref "U3") (pin "22") (pinfunction "ILIM_22") (pintype "power_in"))
    )
    (net (code "41") (name "Net-(U3-ISET)") (class "Default")
      (node (ref "R28") (pin "2") (pinfunction "2_2") (pintype "power_in"))
      (node (ref "U3") (pin "10") (pinfunction "ISET_10") (pintype "power_in"))
    )
    (net (code "42") (name "Net-(U3-PMID)") (class "Default")
      (node (ref "C11") (pin "1") (pinfunction "1_1") (pintype "passive"))
      (node (ref "U3") (pin "20") (pinfunction "PMID_20") (pintype "power_in"))
    )
    (net (code "43") (name "Net-(U3-TS)") (class "Default")
      (node (ref "R20") (pin "1") (pinfunction "1_1") (pintype "power_in"))
      (node (ref "R21") (pin "2") (pinfunction "2_2") (pintype "power_in"))
      (node (ref "U3") (pin "9") (pinfunction "TS_9") (pintype "power_in"))
    )
    (net (code "44") (name "Net-(U3-VDPM)") (class "Default")
      (node (ref "R26") (pin "1") (pinfunction "1_1") (pintype "power_in"))
      (node (ref "R27") (pin "2") (pinfunction "2_2") (pintype "power_in"))
      (node (ref "U3") (pin "23") (pinfunction "VDPM_23") (pintype "power_in"))
    )
    (net (code "45") (name "Net-(U4-FB)") (class "Default")
      (node (ref "R1") (pin "1") (pinfunction "1_1") (pintype "power_in"))
      (node (ref "R2") (pin "2") (pinfunction "2_2") (pintype "power_in"))
      (node (ref "U4") (pin "4") (pinfunction "FB_4") (pintype "passive"))
    )
    (net (code "46") (name "Net-(U4-MODE)") (class "Default")
      (node (ref "R4") (pin "2") (pinfunction "2_2") (pintype "power_in"))
      (node (ref "U4") (pin "10") (pinfunction "MODE_10") (pintype "passive"))
    )
    (net (code "47") (name "Net-(U4-PG)") (class "Default")
      (node (ref "R3") (pin "1") (pinfunction "1_1") (pintype "power_in"))
      (node (ref "U4") (pin "5") (pinfunction "PG_5") (pintype "passive"))
    )
    (net (code "48") (name "Net-(U4-SS{slash}TR)") (class "Default")
      (node (ref "C10") (pin "2") (pinfunction "2_2") (pintype "passive"))
      (node (ref "U4") (pin "9") (pinfunction "SS/TR_9") (pintype "passive"))
    )
    (net (code "49") (name "Net-(U4-SW)") (class "Default")
      (node (ref "L1") (pin "1") (pinfunction "Vcc_1") (pintype "passive"))
      (node (ref "U4") (pin "2") (pinfunction "SW_2") (pintype "passive"))
    )
    (net (code "50") (name "Net-(U5-BI{slash}TOUT)") (class "Default")
      (node (ref "C28") (pin "2") (pinfunction "2_2") (pintype "passive"))
      (node (ref "R22") (pin "2") (pinfunction "2_2") (pintype "power_in"))
      (node (ref "R23") (pin "2") (pinfunction "2_2") (pintype "power_in"))
      (node (ref "U5") (pin "E3") (pinfunction "BI/TOUT_E3") (pintype "passive"))
    )
    (net (code "51") (name "Net-(U5-TS)") (class "Default")
      (node (ref "C44") (pin "2") (pinfunction "2_2") (pintype "passive"))
      (node (ref "R24") (pin "2") (pinfunction "2_2") (pintype "power_in"))
      (node (ref "U5") (pin "D3") (pinfunction "TS_D3") (pintype "passive"))
    )
    (net (code "52") (name "VBUS") (class "Default")
      (node (ref "C23") (pin "1") (pinfunction "1_1") (pintype "passive"))
      (node (ref "C39") (pin "2") (pinfunction "2_2") (pintype "passive"))
      (node (ref "FB1") (pin "1") (pinfunction "Vcc_1") (pintype "passive"))
      (node (ref "Q1") (pin "5") (pinfunction "D_5") (pintype "power_in"))
      (node (ref "Q1") (pin "6") (pinfunction "D_6") (pintype "passive"))
      (node (ref "Q1") (pin "7") (pinfunction "D_7") (pintype "passive"))
      (node (ref "Q1") (pin "8") (pinfunction "D_8") (pintype "passive"))
      (node (ref "U2") (pin "18") (pinfunction "VBUS_SENSE_18") (pintype "power_in"))
      (node (ref "U7") (pin "5") (pinfunction "VBUS_5") (pintype "passive"))
    )
    (net (code "53") (name "VCC_+1.5V") (class "Default")
      (node (ref "C68") (pin "2") (pinfunction "2_2") (pintype "passive"))
      (node (ref "U12") (pin "B1") (pinfunction "VOUT_B1") (pintype "power_in"))
    )
    (net (code "54") (name "VCC_+3V3") (class "Default")
      (node (ref "C29") (pin "2") (pinfunction "2_2") (pintype "passive"))
      (node (ref "C31") (pin "1") (pinfunction "1_1") (pintype "passive"))
      (node (ref "U2") (pin "22") (pinfunction "VSYS_22") (pintype "power_in"))
      (node (ref "U6") (pin "B1") (pinfunction "VOUT_B1") (pintype "power_in"))
    )
    (net (code "55") (name "VCC_2V8") (class "Default")
      (node (ref "C40") (pin "2") (pinfunction "2_2") (pintype "passive"))
      (node (ref "C7") (pin "1") (pinfunction "1_1") (pintype "passive"))
      (node (ref "L1") (pin "2") (pinfunction "Vcc_2") (pintype "passive"))
      (node (ref "R1") (pin "2") (pinfunction "2_2") (pintype "power_in"))
      (node (ref "R10") (pin "2") (pinfunction "2_2") (pintype "power_in"))
      (node (ref "R11") (pin "2") (pinfunction "2_2") (pintype "power_in"))
      (node (ref "R12") (pin "2") (pinfunction "2_2") (pintype "power_in"))
      (node (ref "R13") (pin "2") (pinfunction "2_2") (pintype "power_in"))
      (node (ref "R14") (pin "2") (pinfunction "2_2") (pintype "power_in"))
      (node (ref "R15") (pin "2") (pinfunction "2_2") (pintype "power_in"))
      (node (ref "R40") (pin "2") (pinfunction "2_2") (pintype "power_in"))
      (node (ref "R41") (pin "2") (pinfunction "2_2") (pintype "power_in"))
      (node (ref "R42") (pin "2") (pinfunction "2_2") (pintype "power_in"))
      (node (ref "R43") (pin "2") (pinfunction "2_2") (pintype "power_in"))
      (node (ref "R6") (pin "2") (pinfunction "2_2") (pintype "power_in"))
      (node (ref "R8") (pin "2") (pinfunction "2_2") (pintype "power_in"))
      (node (ref "R9") (pin "2") (pinfunction "2_2") (pintype "power_in"))
      (node (ref "U4") (pin "3") (pinfunction "VOS_3") (pintype "passive"))
    )
    (net (code "56") (name "VCC_IN") (class "Default")
      (node (ref "C17") (pin "1") (pinfunction "1_1") (pintype "passive"))
      (node (ref "Q2") (pin "5") (pinfunction "D_5") (pintype "power_in"))
      (node (ref "Q2") (pin "6") (pinfunction "D_6") (pintype "passive"))
      (node (ref "Q2") (pin "7") (pinfunction "D_7") (pintype "passive"))
      (node (ref "Q2") (pin "8") (pinfunction "D_8") (pintype "passive"))
      (node (ref "R26") (pin "2") (pinfunction "2_2") (pintype "power_in"))
      (node (ref "U3") (pin "19") (pinfunction "IN_19") (pintype "power_in"))
    )
    (net (code "57") (name "VSYS") (class "Default")
      (node (ref "C19") (pin "1") (pinfunction "1_1") (pintype "passive"))
      (node (ref "C21") (pin "2") (pinfunction "2_2") (pintype "passive"))
      (node (ref "C25") (pin "1") (pinfunction "1_1") (pintype "passive"))
      (node (ref "C30") (pin "1") (pinfunction "1_1") (pintype "passive"))
      (node (ref "C41") (pin "1") (pinfunction "1_1") (pintype "passive"))
      (node (ref "C42") (pin "2") (pinfunction "2_2") (pintype "passive"))
      (node (ref "C46") (pin "2") (pinfunction "2_2") (pintype "passive"))
      (node (ref "C67") (pin "2") (pinfunction "2_2") (pintype "passive"))
      (node (ref "C8") (pin "1") (pinfunction "1_1") (pintype "passive"))
      (node (ref "L2") (pin "2") (pinfunction "Vcc_2") (pintype "passive"))
      (node (ref "R3") (pin "2") (pinfunction "2_2") (pintype "power_in"))
      (node (ref "U12") (pin "A2") (pinfunction "EN_A2") (pintype "power_in"))
      (node (ref "U12") (pin "B2") (pinfunction "VIN_B2") (pintype "power_in"))
      (node (ref "U3") (pin "13") (pinfunction "SYS_13") (pintype "power_in"))
      (node (ref "U3") (pin "14") (pinfunction "SYS_14") (pintype "power_in"))
      (node (ref "U4") (pin "6") (pinfunction "EN_6") (pintype "passive"))
      (node (ref "U4") (pin "7") (pinfunction "PVIN_7") (pintype "passive"))
      (node (ref "U4") (pin "8") (pinfunction "AVIN_8") (pintype "passive"))
      (node (ref "U5") (pin "D2") (pinfunction "CE_D2") (pintype "passive"))
      (node (ref "U5") (pin "E1") (pinfunction "REGIN_E1") (pintype "passive"))
      (node (ref "U6") (pin "A2") (pinfunction "EN_A2") (pintype "power_in"))
      (node (ref "U6") (pin "B2") (pinfunction "VIN_B2") (pintype "power_in"))
    )
    (net (code "58") (name "unconnected-(J1-RX1+-PadB11)") (class "Default")
      (node (ref "J1") (pin "B11") (pinfunction "RX1+_B11") (pintype "passive+no_connect"))
    )
    (net (code "59") (name "unconnected-(J1-RX1--PadB10)") (class "Default")
      (node (ref "J1") (pin "B10") (pinfunction "RX1-_B10") (pintype "passive+no_connect"))
    )
    (net (code "60") (name "unconnected-(J1-RX2+-PadA11)") (class "Default")
      (node (ref "J1") (pin "A11") (pinfunction "RX2+_A11") (pintype "passive+no_connect"))
    )
    (net (code "61") (name "unconnected-(J1-RX2--PadA10)") (class "Default")
      (node (ref "J1") (pin "A10") (pinfunction "RX2-_A10") (pintype "passive+no_connect"))
    )
    (net (code "62") (name "unconnected-(J1-SBU1-PadA8)") (class "Default")
      (node (ref "J1") (pin "A8") (pinfunction "SBU1_A8") (pintype "passive+no_connect"))
    )
    (net (code "63") (name "unconnected-(J1-SBU2-PadB8)") (class "Default")
      (node (ref "J1") (pin "B8") (pinfunction "SBU2_B8") (pintype "passive+no_connect"))
    )
    (net (code "64") (name "unconnected-(J1-TX1+-PadA2)") (class "Default")
      (node (ref "J1") (pin "A2") (pinfunction "TX1+_A2") (pintype "passive+no_connect"))
    )
    (net (code "65") (name "unconnected-(J1-TX1--PadA3)") (class "Default")
      (node (ref "J1") (pin "A3") (pinfunction "TX1-_A3") (pintype "passive+no_connect"))
    )
    (net (code "66") (name "unconnected-(J1-TX2+-PadB2)") (class "Default")
      (node (ref "J1") (pin "B2") (pinfunction "TX2+_B2") (pintype "passive+no_connect"))
    )
    (net (code "67") (name "unconnected-(J1-TX2--PadB3)") (class "Default")
      (node (ref "J1") (pin "B3") (pinfunction "TX2-_B3") (pintype "passive+no_connect"))
    )
    (net (code "68") (name "unconnected-(U2-VBUS_EN_SRC-Pad20)") (class "Default")
      (node (ref "U2") (pin "20") (pinfunction "VBUS_EN_SRC_20") (pintype "power_in+no_connect"))
    )
  )
)
